# uC.net
KiCad netlist of a schematic drawn in Altium Designer
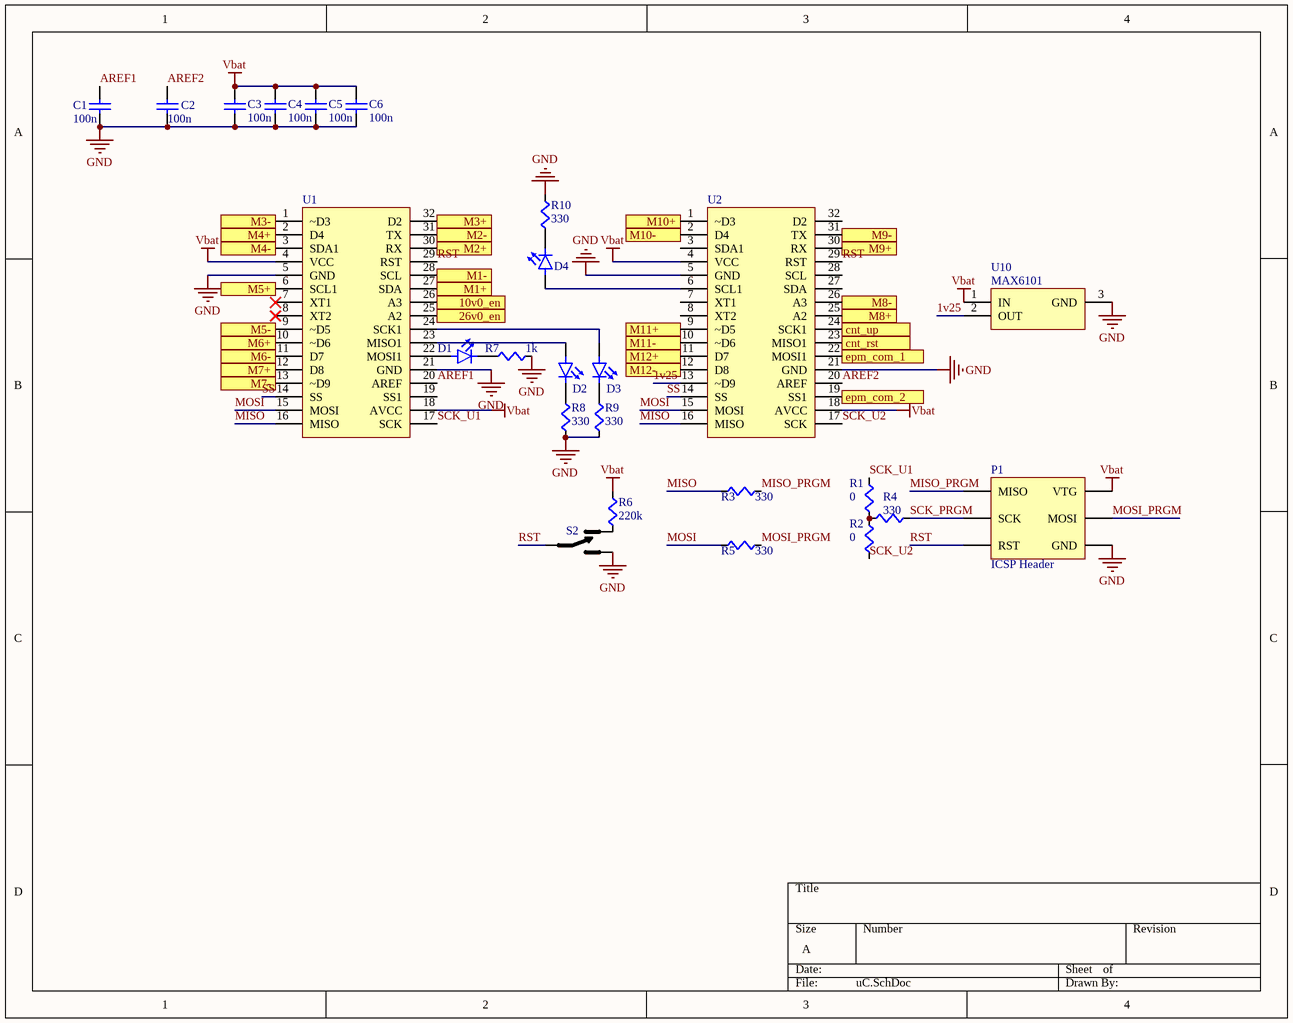
[diagram p0: uC.SchDoc]

(export (version "E")
  (design (tool "Eeschema 10.0.6"))
  (components
    (comp (ref "C1")
      (value "100n")
      (footprint "SMD0603_cap")
      (description "Ceramic Chip Capacitor")
      (fields (field (name "Comment") "Cap"))
      (libsource (lib "Components") (part "Capacitor Ceramic"))
    )
    (comp (ref "C2")
      (value "100n")
      (footprint "SMD0603_cap")
      (description "Ceramic Chip Capacitor")
      (fields (field (name "Comment") "Cap"))
      (libsource (lib "Components") (part "Capacitor Ceramic"))
    )
    (comp (ref "C3")
      (value "100n")
      (footprint "SMD0603_cap")
      (description "Ceramic Chip Capacitor")
      (fields (field (name "Comment") "Cap"))
      (libsource (lib "Components") (part "Capacitor Ceramic"))
    )
    (comp (ref "C4")
      (value "100n")
      (footprint "SMD0603_cap")
      (description "Ceramic Chip Capacitor")
      (fields (field (name "Comment") "Cap"))
      (libsource (lib "Components") (part "Capacitor Ceramic"))
    )
    (comp (ref "C5")
      (value "100n")
      (footprint "SMD0603_cap")
      (description "Ceramic Chip Capacitor")
      (fields (field (name "Comment") "Cap"))
      (libsource (lib "Components") (part "Capacitor Ceramic"))
    )
    (comp (ref "C6")
      (value "100n")
      (footprint "SMD0603_cap")
      (description "Ceramic Chip Capacitor")
      (fields (field (name "Comment") "Cap"))
      (libsource (lib "Components") (part "Capacitor Ceramic"))
    )
    (comp (ref "D1")
      (value "LED")
      (footprint "SMD0603 POLARIZED")
      (libsource (lib "Components") (part "LED"))
    )
    (comp (ref "D2")
      (value "IR_LED")
      (footprint "smd_phototrans")
      (libsource (lib "Components") (part "IR_LED"))
    )
    (comp (ref "D3")
      (value "IR_LED")
      (footprint "smd_phototrans")
      (libsource (lib "Components") (part "IR_LED"))
    )
    (comp (ref "D4")
      (value "IR_LED")
      (footprint "smd_phototrans")
      (libsource (lib "Components") (part "IR_LED"))
    )
    (comp (ref "P1")
      (value "ICSP Header")
      (footprint "icsp_pads")
      (libsource (lib "Components") (part "ICSP Header"))
    )
    (comp (ref "R1")
      (value "0")
      (footprint "SMD0603")
      (description "Resistor")
      (fields (field (name "Comment") "Res"))
      (libsource (lib "Components") (part "Resistor"))
    )
    (comp (ref "R2")
      (value "0")
      (footprint "SMD0603")
      (description "Resistor")
      (fields (field (name "Comment") "Res"))
      (libsource (lib "Components") (part "Resistor"))
    )
    (comp (ref "R3")
      (value "330")
      (footprint "SMD0603")
      (description "Resistor")
      (fields (field (name "Comment") "Res"))
      (libsource (lib "Components") (part "Resistor"))
    )
    (comp (ref "R4")
      (value "330")
      (footprint "SMD0603")
      (description "Resistor")
      (fields (field (name "Comment") "Res"))
      (libsource (lib "Components") (part "Resistor"))
    )
    (comp (ref "R5")
      (value "330")
      (footprint "SMD0603")
      (description "Resistor")
      (fields (field (name "Comment") "Res"))
      (libsource (lib "Components") (part "Resistor"))
    )
    (comp (ref "R6")
      (value "220k")
      (footprint "SMD0603")
      (description "Resistor")
      (fields (field (name "Comment") "Res"))
      (libsource (lib "Components") (part "Resistor"))
    )
    (comp (ref "R7")
      (value "1k")
      (footprint "SMD0603")
      (description "Resistor")
      (fields (field (name "Comment") "Res"))
      (libsource (lib "Components") (part "Resistor"))
    )
    (comp (ref "R8")
      (value "330")
      (footprint "SMD0603")
      (description "Resistor")
      (fields (field (name "Comment") "Res"))
      (libsource (lib "Components") (part "Resistor"))
    )
    (comp (ref "R9")
      (value "330")
      (footprint "SMD0603")
      (description "Resistor")
      (fields (field (name "Comment") "Res"))
      (libsource (lib "Components") (part "Resistor"))
    )
    (comp (ref "R10")
      (value "330")
      (footprint "SMD0603")
      (description "Resistor")
      (fields (field (name "Comment") "Res"))
      (libsource (lib "Components") (part "Resistor"))
    )
    (comp (ref "S2")
      (value "Switch_SPDT")
      (footprint "Switch_SPDT")
      (libsource (lib "Components") (part "Switch_SPDT"))
    )
    (comp (ref "U1")
      (value "ATMega328P_vqfn")
      (footprint "vqfn-32")
      (libsource (lib "Components") (part "ATMega328P_vqfn"))
    )
    (comp (ref "U2")
      (value "ATMega328P_vqfn")
      (footprint "vqfn-32")
      (libsource (lib "Components") (part "ATMega328P_vqfn"))
    )
    (comp (ref "U10") (value "MAX6101") (footprint "sot23") (libsource (lib "Components") (part "MAX6101")))
  )
  (nets
    (net (code "1") (name "/1v25") (class "Default")
      (node (ref "U10") (pin "2") (pinfunction "OUT_2") (pintype "passive"))
      (node (ref "U2") (pin "13") (pinfunction "~D9_13") (pintype "passive"))
    )
    (net (code "2") (name "/10v0_en") (class "Default")
      (node (ref "U1") (pin "26") (pinfunction "A3_26") (pintype "passive"))
    )
    (net (code "3") (name "/26v0_en") (class "Default")
      (node (ref "U1") (pin "25") (pinfunction "A2_25") (pintype "passive"))
    )
    (net (code "4") (name "/AREF1") (class "Default")
      (node (ref "C1") (pin "2") (pinfunction "2_2") (pintype "passive"))
      (node (ref "U1") (pin "20") (pinfunction "AREF_20") (pintype "passive"))
    )
    (net (code "5") (name "/AREF2") (class "Default")
      (node (ref "C2") (pin "2") (pinfunction "2_2") (pintype "passive"))
      (node (ref "U2") (pin "20") (pinfunction "AREF_20") (pintype "passive"))
    )
    (net (code "6") (name "/M1+") (class "Default")
      (node (ref "U1") (pin "27") (pinfunction "SDA_27") (pintype "passive"))
    )
    (net (code "7") (name "/M1-") (class "Default")
      (node (ref "U1") (pin "28") (pinfunction "SCL_28") (pintype "passive"))
    )
    (net (code "8") (name "/M2+") (class "Default")
      (node (ref "U1") (pin "30") (pinfunction "RX_30") (pintype "passive"))
    )
    (net (code "9") (name "/M2-") (class "Default")
      (node (ref "U1") (pin "31") (pinfunction "TX_31") (pintype "passive"))
    )
    (net (code "10") (name "/M3+") (class "Default")
      (node (ref "U1") (pin "32") (pinfunction "D2_32") (pintype "passive"))
    )
    (net (code "11") (name "/M3-") (class "Default")
      (node (ref "U1") (pin "1") (pinfunction "~D3_1") (pintype "passive"))
    )
    (net (code "12") (name "/M4+") (class "Default")
      (node (ref "U1") (pin "2") (pinfunction "D4_2") (pintype "passive"))
    )
    (net (code "13") (name "/M4-") (class "Default")
      (node (ref "U1") (pin "3") (pinfunction "SDA1_3") (pintype "passive"))
    )
    (net (code "14") (name "/M5+") (class "Default")
      (node (ref "U1") (pin "6") (pinfunction "SCL1_6") (pintype "passive"))
    )
    (net (code "15") (name "/M5-") (class "Default")
      (node (ref "U1") (pin "9") (pinfunction "~D5_9") (pintype "passive"))
    )
    (net (code "16") (name "/M6+") (class "Default")
      (node (ref "U1") (pin "10") (pinfunction "~D6_10") (pintype "passive"))
    )
    (net (code "17") (name "/M6-") (class "Default")
      (node (ref "U1") (pin "11") (pinfunction "D7_11") (pintype "passive"))
    )
    (net (code "18") (name "/M7+") (class "Default")
      (node (ref "U1") (pin "12") (pinfunction "D8_12") (pintype "passive"))
    )
    (net (code "19") (name "/M7-") (class "Default")
      (node (ref "U1") (pin "13") (pinfunction "~D9_13") (pintype "passive"))
    )
    (net (code "20") (name "/M8+") (class "Default")
      (node (ref "U2") (pin "25") (pinfunction "A2_25") (pintype "passive"))
    )
    (net (code "21") (name "/M8-") (class "Default")
      (node (ref "U2") (pin "26") (pinfunction "A3_26") (pintype "passive"))
    )
    (net (code "22") (name "/M9+") (class "Default")
      (node (ref "U2") (pin "30") (pinfunction "RX_30") (pintype "passive"))
    )
    (net (code "23") (name "/M9-") (class "Default")
      (node (ref "U2") (pin "31") (pinfunction "TX_31") (pintype "passive"))
    )
    (net (code "24") (name "/M10+") (class "Default")
      (node (ref "U2") (pin "1") (pinfunction "~D3_1") (pintype "passive"))
    )
    (net (code "25") (name "/M10-") (class "Default")
      (node (ref "U2") (pin "2") (pinfunction "D4_2") (pintype "passive"))
    )
    (net (code "26") (name "/M11+") (class "Default")
      (node (ref "U2") (pin "9") (pinfunction "~D5_9") (pintype "passive"))
    )
    (net (code "27") (name "/M11-") (class "Default")
      (node (ref "U2") (pin "10") (pinfunction "~D6_10") (pintype "passive"))
    )
    (net (code "28") (name "/M12+") (class "Default")
      (node (ref "U2") (pin "11") (pinfunction "D7_11") (pintype "passive"))
    )
    (net (code "29") (name "/M12-") (class "Default")
      (node (ref "U2") (pin "12") (pinfunction "D8_12") (pintype "passive"))
    )
    (net (code "30") (name "/MISO") (class "Default")
      (node (ref "R3") (pin "2") (pinfunction "2_2") (pintype "passive"))
      (node (ref "U1") (pin "16") (pinfunction "MISO_16") (pintype "passive"))
      (node (ref "U2") (pin "16") (pinfunction "MISO_16") (pintype "passive"))
    )
    (net (code "31") (name "/MISO_PRGM") (class "Default")
      (node (ref "P1") (pin "1") (pinfunction "MISO_1") (pintype "passive"))
      (node (ref "R3") (pin "1") (pinfunction "1_1") (pintype "passive"))
    )
    (net (code "32") (name "/MOSI") (class "Default")
      (node (ref "R5") (pin "2") (pinfunction "2_2") (pintype "passive"))
      (node (ref "U1") (pin "15") (pinfunction "MOSI_15") (pintype "passive"))
      (node (ref "U2") (pin "15") (pinfunction "MOSI_15") (pintype "passive"))
    )
    (net (code "33") (name "/MOSI_PRGM") (class "Default")
      (node (ref "P1") (pin "4") (pinfunction "MOSI_4") (pintype "passive"))
      (node (ref "R5") (pin "1") (pinfunction "1_1") (pintype "passive"))
    )
    (net (code "34") (name "/RST") (class "Default")
      (node (ref "P1") (pin "5") (pinfunction "RST_5") (pintype "passive"))
      (node (ref "S2") (pin "2") (pintype "passive"))
      (node (ref "U1") (pin "29") (pinfunction "RST_29") (pintype "passive"))
      (node (ref "U2") (pin "29") (pinfunction "RST_29") (pintype "passive"))
    )
    (net (code "35") (name "/SCK_PRGM") (class "Default")
      (node (ref "P1") (pin "3") (pinfunction "SCK_3") (pintype "passive"))
      (node (ref "R4") (pin "1") (pinfunction "1_1") (pintype "passive"))
    )
    (net (code "36") (name "/SCK_U1") (class "Default")
      (node (ref "R1") (pin "2") (pinfunction "2_2") (pintype "passive"))
      (node (ref "U1") (pin "17") (pinfunction "SCK_17") (pintype "passive"))
    )
    (net (code "37") (name "/SCK_U2") (class "Default")
      (node (ref "R2") (pin "1") (pinfunction "1_1") (pintype "passive"))
      (node (ref "U2") (pin "17") (pinfunction "SCK_17") (pintype "passive"))
    )
    (net (code "38") (name "/SS") (class "Default")
      (node (ref "U1") (pin "14") (pinfunction "SS_14") (pintype "passive"))
      (node (ref "U2") (pin "14") (pinfunction "SS_14") (pintype "passive"))
    )
    (net (code "39") (name "/cnt_rst") (class "Default")
      (node (ref "U2") (pin "23") (pinfunction "MISO1_23") (pintype "passive"))
    )
    (net (code "40") (name "/cnt_up") (class "Default")
      (node (ref "U2") (pin "24") (pinfunction "SCK1_24") (pintype "passive"))
    )
    (net (code "41") (name "/epm_com_1") (class "Default")
      (node (ref "U2") (pin "22") (pinfunction "MOSI1_22") (pintype "passive"))
    )
    (net (code "42") (name "/epm_com_2") (class "Default")
      (node (ref "U2") (pin "19") (pinfunction "SS1_19") (pintype "passive"))
    )
    (net (code "43") (name "GND") (class "Default")
      (node (ref "C1") (pin "1") (pinfunction "1_1") (pintype "passive"))
      (node (ref "C2") (pin "1") (pinfunction "1_1") (pintype "passive"))
      (node (ref "C3") (pin "1") (pinfunction "1_1") (pintype "passive"))
      (node (ref "C4") (pin "1") (pinfunction "1_1") (pintype "passive"))
      (node (ref "C5") (pin "1") (pinfunction "1_1") (pintype "passive"))
      (node (ref "C6") (pin "1") (pinfunction "1_1") (pintype "passive"))
      (node (ref "P1") (pin "6") (pinfunction "GND_6") (pintype "passive"))
      (node (ref "R10") (pin "1") (pinfunction "1_1") (pintype "passive"))
      (node (ref "R7") (pin "2") (pinfunction "2_2") (pintype "passive"))
      (node (ref "R8") (pin "1") (pinfunction "1_1") (pintype "passive"))
      (node (ref "R9") (pin "1") (pinfunction "1_1") (pintype "passive"))
      (node (ref "S2") (pin "1") (pintype "passive"))
      (node (ref "U1") (pin "21") (pinfunction "GND_21") (pintype "passive"))
      (node (ref "U1") (pin "5") (pinfunction "GND_5") (pintype "passive"))
      (node (ref "U10") (pin "3") (pinfunction "GND_3") (pintype "passive"))
      (node (ref "U2") (pin "21") (pinfunction "GND_21") (pintype "passive"))
      (node (ref "U2") (pin "5") (pinfunction "GND_5") (pintype "passive"))
    )
    (net (code "44") (name "Net-(D1-Anode_(+))") (class "Default")
      (node (ref "D1") (pin "1") (pinfunction "Anode_(+)_1") (pintype "passive"))
      (node (ref "U1") (pin "22") (pinfunction "MOSI1_22") (pintype "passive"))
    )
    (net (code "45") (name "Net-(D1-Cathode_(-))") (class "Default")
      (node (ref "D1") (pin "2") (pinfunction "Cathode_(-)_2") (pintype "passive"))
      (node (ref "R7") (pin "1") (pinfunction "1_1") (pintype "passive"))
    )
    (net (code "46") (name "Net-(D2-Anode_(+))") (class "Default")
      (node (ref "D2") (pin "1") (pinfunction "Anode_(+)_1") (pintype "passive"))
      (node (ref "U1") (pin "23") (pinfunction "MISO1_23") (pintype "passive"))
    )
    (net (code "47") (name "Net-(D2-Cathode_(-))") (class "Default")
      (node (ref "D2") (pin "2") (pinfunction "Cathode_(-)_2") (pintype "passive"))
      (node (ref "R8") (pin "2") (pinfunction "2_2") (pintype "passive"))
    )
    (net (code "48") (name "Net-(D3-Anode_(+))") (class "Default")
      (node (ref "D3") (pin "1") (pinfunction "Anode_(+)_1") (pintype "passive"))
      (node (ref "U1") (pin "24") (pinfunction "SCK1_24") (pintype "passive"))
    )
    (net (code "49") (name "Net-(D3-Cathode_(-))") (class "Default")
      (node (ref "D3") (pin "2") (pinfunction "Cathode_(-)_2") (pintype "passive"))
      (node (ref "R9") (pin "2") (pinfunction "2_2") (pintype "passive"))
    )
    (net (code "50") (name "Net-(D4-Anode_(+))") (class "Default")
      (node (ref "D4") (pin "1") (pinfunction "Anode_(+)_1") (pintype "passive"))
      (node (ref "U2") (pin "6") (pinfunction "SCL1_6") (pintype "passive"))
    )
    (net (code "51") (name "Net-(D4-Cathode_(-))") (class "Default")
      (node (ref "D4") (pin "2") (pinfunction "Cathode_(-)_2") (pintype "passive"))
      (node (ref "R10") (pin "2") (pinfunction "2_2") (pintype "passive"))
    )
    (net (code "52") (name "Net-(R1-Pad1)") (class "Default")
      (node (ref "R1") (pin "1") (pinfunction "1_1") (pintype "passive"))
      (node (ref "R2") (pin "2") (pinfunction "2_2") (pintype "passive"))
      (node (ref "R4") (pin "2") (pinfunction "2_2") (pintype "passive"))
    )
    (net (code "53") (name "Net-(R6-Pad2)") (class "Default")
      (node (ref "R6") (pin "2") (pinfunction "2_2") (pintype "passive"))
      (node (ref "S2") (pin "3") (pintype "passive"))
    )
    (net (code "54") (name "Vbat") (class "Default")
      (node (ref "C3") (pin "2") (pinfunction "2_2") (pintype "passive"))
      (node (ref "C4") (pin "2") (pinfunction "2_2") (pintype "passive"))
      (node (ref "C5") (pin "2") (pinfunction "2_2") (pintype "passive"))
      (node (ref "C6") (pin "2") (pinfunction "2_2") (pintype "passive"))
      (node (ref "P1") (pin "2") (pinfunction "VTG_2") (pintype "passive"))
      (node (ref "R6") (pin "1") (pinfunction "1_1") (pintype "passive"))
      (node (ref "U1") (pin "18") (pinfunction "AVCC_18") (pintype "passive"))
      (node (ref "U1") (pin "4") (pinfunction "VCC_4") (pintype "passive"))
      (node (ref "U10") (pin "1") (pinfunction "IN_1") (pintype "passive"))
      (node (ref "U2") (pin "18") (pinfunction "AVCC_18") (pintype "passive"))
      (node (ref "U2") (pin "4") (pinfunction "VCC_4") (pintype "passive"))
    )
    (net (code "55") (name "unconnected-(U1-SS1-Pad19)") (class "Default")
      (node (ref "U1") (pin "19") (pinfunction "SS1_19") (pintype "passive"))
    )
    (net (code "56") (name "unconnected-(U1-XT1-Pad7)") (class "Default")
      (node (ref "U1") (pin "7") (pinfunction "XT1_7") (pintype "passive+no_connect"))
    )
    (net (code "57") (name "unconnected-(U1-XT2-Pad8)") (class "Default")
      (node (ref "U1") (pin "8") (pinfunction "XT2_8") (pintype "passive+no_connect"))
    )
    (net (code "58") (name "unconnected-(U2-D2-Pad32)") (class "Default")
      (node (ref "U2") (pin "32") (pinfunction "D2_32") (pintype "passive"))
    )
    (net (code "59") (name "unconnected-(U2-SCL-Pad28)") (class "Default")
      (node (ref "U2") (pin "28") (pinfunction "SCL_28") (pintype "passive"))
    )
    (net (code "60") (name "unconnected-(U2-SDA-Pad27)") (class "Default")
      (node (ref "U2") (pin "27") (pinfunction "SDA_27") (pintype "passive"))
    )
    (net (code "61") (name "unconnected-(U2-SDA1-Pad3)") (class "Default")
      (node (ref "U2") (pin "3") (pinfunction "SDA1_3") (pintype "passive"))
    )
    (net (code "62") (name "unconnected-(U2-XT1-Pad7)") (class "Default")
      (node (ref "U2") (pin "7") (pinfunction "XT1_7") (pintype "passive"))
    )
    (net (code "63") (name "unconnected-(U2-XT2-Pad8)") (class "Default")
      (node (ref "U2") (pin "8") (pinfunction "XT2_8") (pintype "passive"))
    )
  )
)
